# Supply_0.net
KiCad netlist of a schematic drawn in Altium Designer
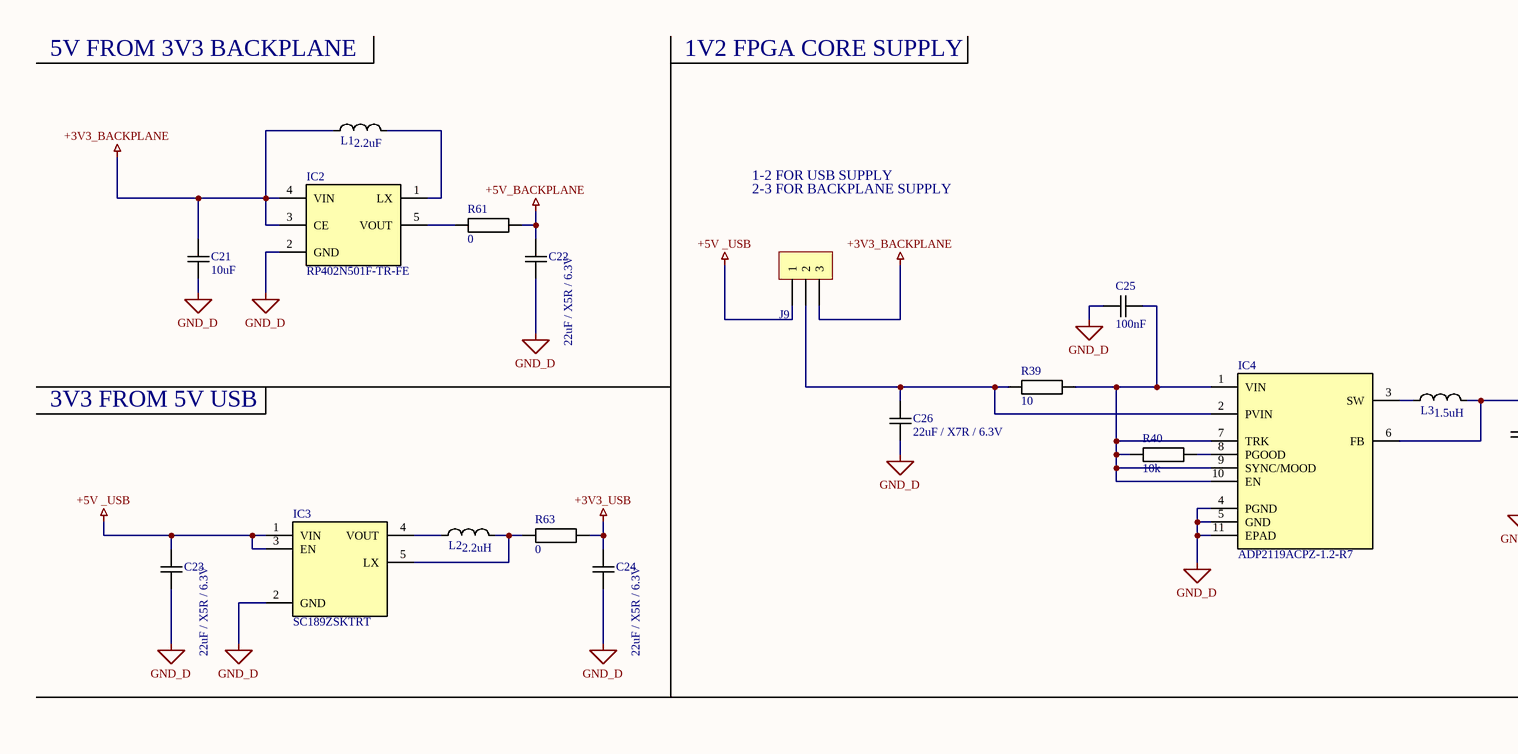
[diagram p0: Supply_0.SchDoc, left]
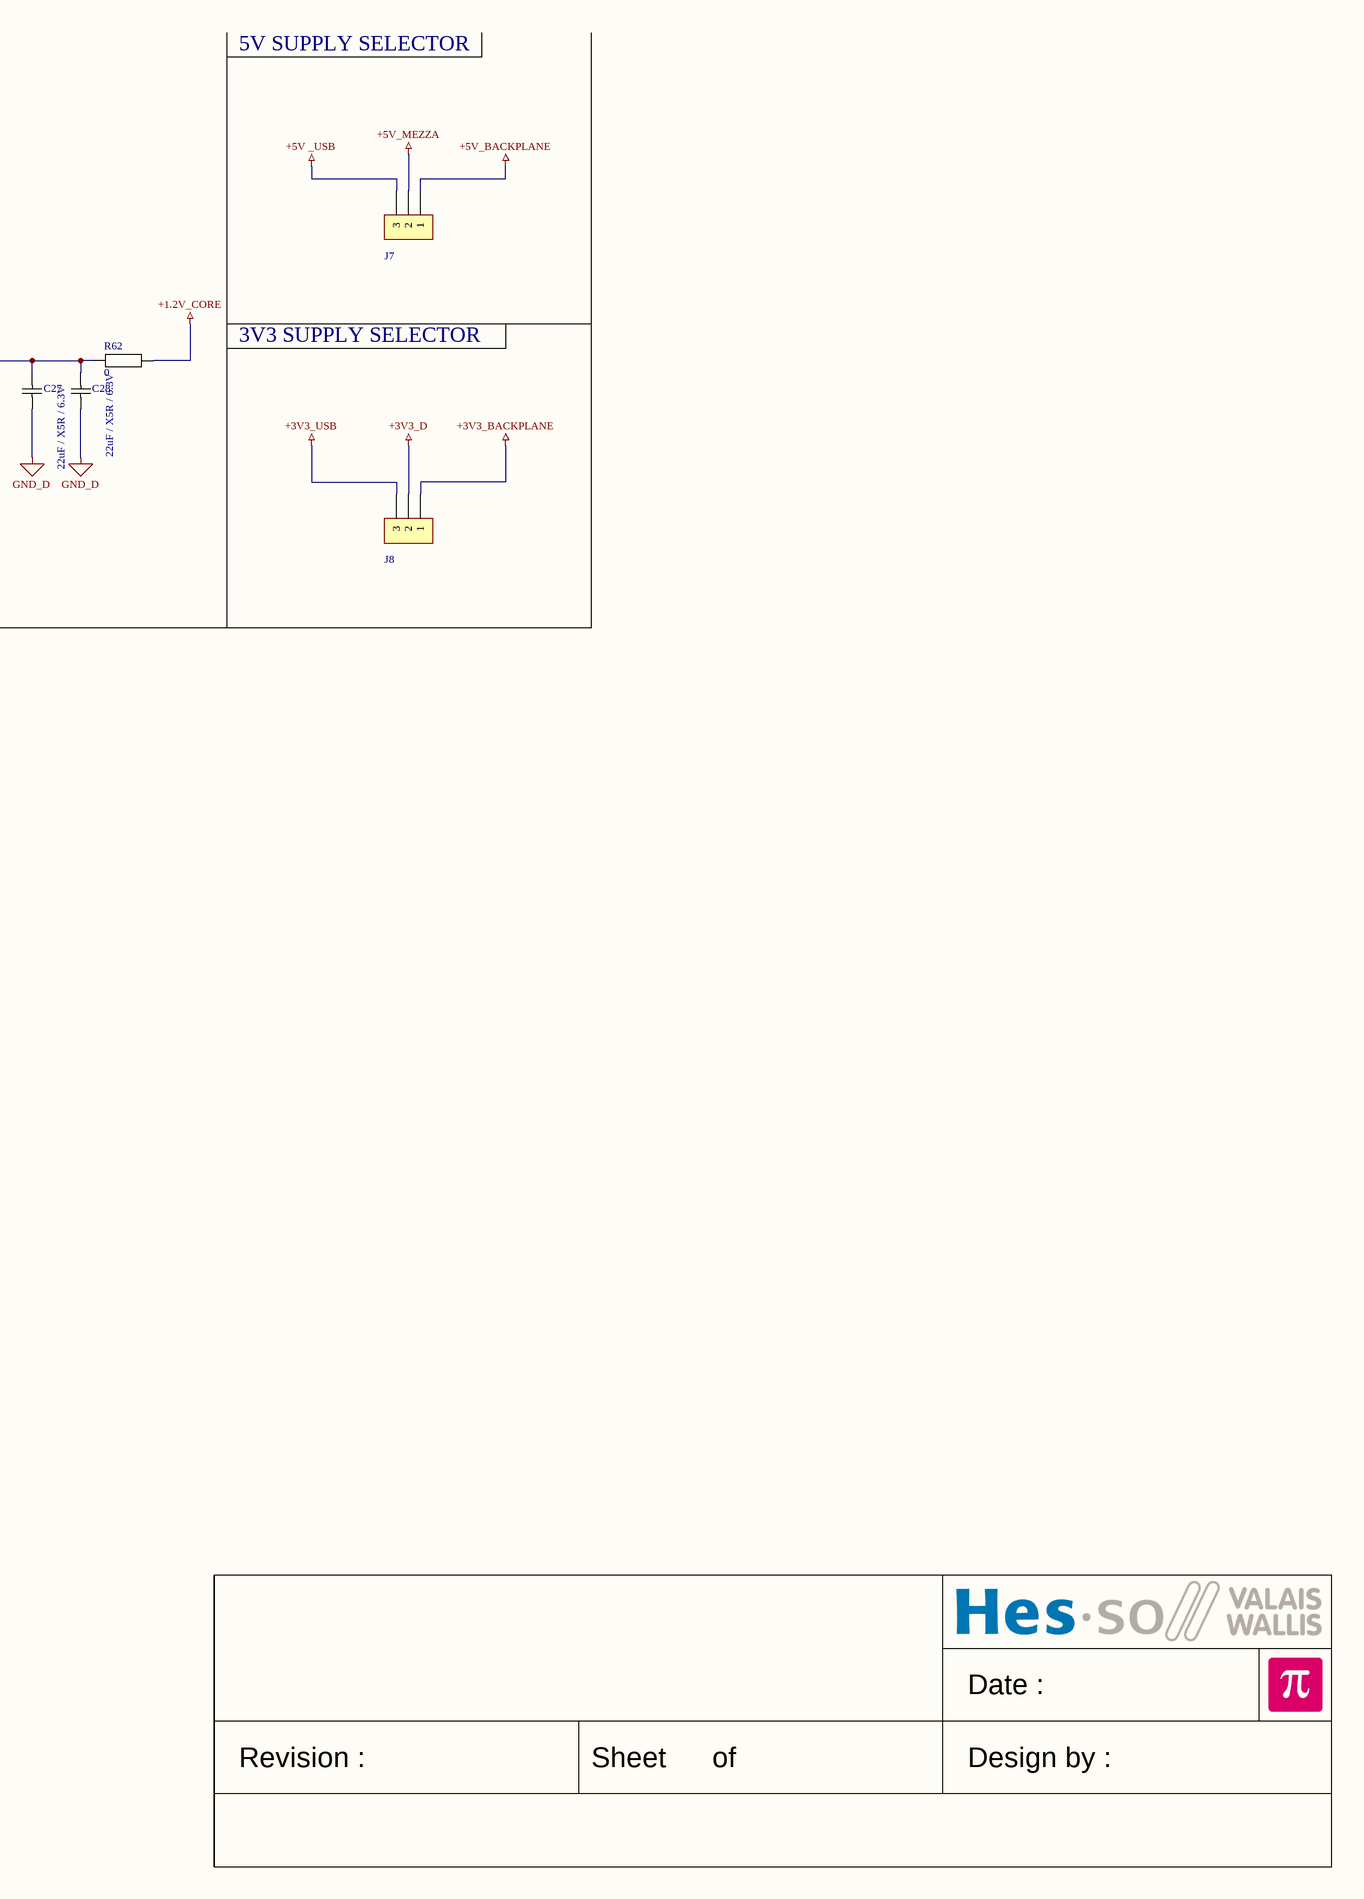
[diagram p1: Supply_0.SchDoc, right]

(export (version "E")
  (design (tool "Eeschema 10.0.6"))
  (components
    (comp (ref "C21")
      (value "10uF")
      (footprint "CAPACITOR 2012 REFLOW")
      (description "Capacitor")
      (libsource (lib "Capacitor") (part "Capacitor"))
    )
    (comp (ref "C22")
      (value "22uF / X5R / 6.3V")
      (footprint "CAPACITOR 2012 REFLOW")
      (description "Capacitor")
      (libsource (lib "Capacitor") (part "Capacitor"))
    )
    (comp (ref "C23")
      (value "22uF / X5R / 6.3V")
      (footprint "CAPACITOR 2012 REFLOW")
      (description "Capacitor")
      (libsource (lib "Capacitor") (part "Capacitor"))
    )
    (comp (ref "C24")
      (value "22uF / X5R / 6.3V")
      (footprint "CAPACITOR 2012 REFLOW")
      (description "Capacitor")
      (libsource (lib "Capacitor") (part "Capacitor"))
    )
    (comp (ref "C25")
      (value "100nF")
      (footprint "CAPACITOR 1608 REFLOW")
      (description "Capacitor")
      (libsource (lib "Capacitor") (part "Capacitor"))
    )
    (comp (ref "C26")
      (value "22uF / X7R / 6.3V")
      (footprint "CAPACITOR 2012 REFLOW")
      (description "Capacitor")
      (libsource (lib "Capacitor") (part "Capacitor"))
    )
    (comp (ref "C27")
      (value "22uF / X5R / 6.3V")
      (footprint "CAPACITOR 2012 REFLOW")
      (description "Capacitor")
      (libsource (lib "Capacitor") (part "Capacitor"))
    )
    (comp (ref "C28")
      (value "22uF / X5R / 6.3V")
      (footprint "CAPACITOR 2012 REFLOW")
      (description "Capacitor")
      (libsource (lib "Capacitor") (part "Capacitor"))
    )
    (comp (ref "IC2")
      (value "RP402N501F-TR-FE")
      (footprint "SamacSys:SOT95P280X130-5N")
      (description "Integrated Circuit")
      (fields (field (name "MOUSER PART NUMBER") "848-RP402N501F-TR-FE"))
      (libsource (lib "SamacSys") (part "RP402N501F-TR-FE"))
    )
    (comp (ref "IC3")
      (value "SC189ZSKTRT")
      (footprint "SamacSys:SOT95P280X145-5N")
      (description "Integrated Circuit")
      (fields (field (name "MOUSER PART NUMBER") "947-SC189ZSKTRT"))
      (libsource (lib "SamacSys") (part "SC189ZSKTRT"))
    )
    (comp (ref "IC4")
      (value "ADP2119ACPZ-1.2-R7")
      (footprint "SamacSys:SON50P300X300X85-11N")
      (description "Integrated Circuit")
      (fields (field (name "MOUSER PART NUMBER") "584-ADP2119ACPZ1.2R7"))
      (libsource (lib "SamacSys") (part "ADP2119ACPZ-1.2-R7"))
    )
    (comp (ref "J7")
      (value "*")
      (footprint "PinHeader1x3 P2.54")
      (description "Plug connector")
      (libsource (lib "PinHeader") (part "PinHeader1x3"))
    )
    (comp (ref "J8")
      (value "*")
      (footprint "PinHeader1x3 P2.54")
      (description "Plug connector")
      (libsource (lib "PinHeader") (part "PinHeader1x3"))
    )
    (comp (ref "J9")
      (value "*")
      (footprint "PinHeader1x3 P2.54")
      (description "Plug connector")
      (libsource (lib "") (part "PinHeader1x3_1"))
    )
    (comp (ref "L1")
      (value "2.2uF")
      (footprint "TDK VLCF5020-1")
      (description "Inductor")
      (libsource (lib "Inductor") (part "Inductor"))
    )
    (comp (ref "L2")
      (value "2.2uH")
      (footprint "TDK VLCF5020-1")
      (description "Inductor")
      (libsource (lib "Inductor") (part "Inductor"))
    )
    (comp (ref "L3")
      (value "1.5uH")
      (footprint "TDK VLCF5020-1")
      (description "Inductor")
      (libsource (lib "Inductor") (part "Inductor"))
    )
    (comp (ref "R39")
      (value "10")
      (footprint "RESISTOR 2012 REFLOW")
      (description "Resistor 1% 50V 125mW 2012(0805)")
      (libsource (lib "Resistor") (part "Resistor"))
    )
    (comp (ref "R40")
      (value "10k")
      (footprint "RESISTOR 2012 REFLOW")
      (description "Resistor 1% 50V 125mW 2012(0805)")
      (libsource (lib "Resistor") (part "Resistor"))
    )
    (comp (ref "R61")
      (value "0")
      (footprint "RESISTOR 1608 REFLOW")
      (description "Resistor 1% 50V 100mW 1608(0603)")
      (libsource (lib "Resistor") (part "Resistor"))
    )
    (comp (ref "R62")
      (value "0")
      (footprint "RESISTOR 1608 REFLOW")
      (description "Resistor 1% 50V 100mW 1608(0603)")
      (libsource (lib "Resistor") (part "Resistor"))
    )
    (comp (ref "R63")
      (value "0")
      (footprint "RESISTOR 1608 REFLOW")
      (description "Resistor 1% 50V 100mW 1608(0603)")
      (libsource (lib "Resistor") (part "Resistor"))
    )
  )
  (nets
    (net (code "1") (name "+1.2V_CORE") (class "Default")
      (node (ref "R62") (pin "2") (pinfunction "2_2") (pintype "passive"))
    )
    (net (code "2") (name "+3V3_BACKPLANE") (class "Default")
      (node (ref "C21") (pin "2") (pinfunction "2_2") (pintype "passive"))
      (node (ref "IC2") (pin "3") (pinfunction "CE_3") (pintype "passive"))
      (node (ref "IC2") (pin "4") (pinfunction "VIN_4") (pintype "passive"))
      (node (ref "J8") (pin "1") (pinfunction "1_1") (pintype "passive"))
      (node (ref "J9") (pin "3") (pinfunction "3_3") (pintype "passive"))
      (node (ref "L1") (pin "1") (pinfunction "1_1") (pintype "passive"))
    )
    (net (code "3") (name "+3V3_D") (class "Default")
      (node (ref "J8") (pin "2") (pinfunction "2_2") (pintype "passive"))
    )
    (net (code "4") (name "+3V3_USB") (class "Default")
      (node (ref "C24") (pin "2") (pinfunction "2_2") (pintype "passive"))
      (node (ref "J8") (pin "3") (pinfunction "3_3") (pintype "passive"))
      (node (ref "R63") (pin "2") (pinfunction "2_2") (pintype "passive"))
    )
    (net (code "5") (name "+5V _USB") (class "Default")
      (node (ref "C23") (pin "2") (pinfunction "2_2") (pintype "passive"))
      (node (ref "IC3") (pin "1") (pinfunction "VIN_1") (pintype "passive"))
      (node (ref "IC3") (pin "3") (pinfunction "EN_3") (pintype "passive"))
      (node (ref "J7") (pin "3") (pinfunction "3_3") (pintype "passive"))
      (node (ref "J9") (pin "1") (pinfunction "1_1") (pintype "passive"))
    )
    (net (code "6") (name "+5V_BACKPLANE") (class "Default")
      (node (ref "C22") (pin "2") (pinfunction "2_2") (pintype "passive"))
      (node (ref "J7") (pin "1") (pinfunction "1_1") (pintype "passive"))
      (node (ref "R61") (pin "2") (pinfunction "2_2") (pintype "passive"))
    )
    (net (code "7") (name "+5V_MEZZA") (class "Default")
      (node (ref "J7") (pin "2") (pinfunction "2_2") (pintype "passive"))
    )
    (net (code "8") (name "GND_D") (class "Default")
      (node (ref "C21") (pin "1") (pinfunction "1_1") (pintype "passive"))
      (node (ref "C22") (pin "1") (pinfunction "1_1") (pintype "passive"))
      (node (ref "C23") (pin "1") (pinfunction "1_1") (pintype "passive"))
      (node (ref "C24") (pin "1") (pinfunction "1_1") (pintype "passive"))
      (node (ref "C25") (pin "2") (pinfunction "2_2") (pintype "passive"))
      (node (ref "C26") (pin "1") (pinfunction "1_1") (pintype "passive"))
      (node (ref "C27") (pin "1") (pinfunction "1_1") (pintype "passive"))
      (node (ref "C28") (pin "1") (pinfunction "1_1") (pintype "passive"))
      (node (ref "IC2") (pin "2") (pinfunction "GND_2") (pintype "passive"))
      (node (ref "IC3") (pin "2") (pinfunction "GND_2") (pintype "passive"))
      (node (ref "IC4") (pin "11") (pinfunction "EPAD_11") (pintype "passive"))
      (node (ref "IC4") (pin "4") (pinfunction "PGND_4") (pintype "passive"))
      (node (ref "IC4") (pin "5") (pinfunction "GND_5") (pintype "passive"))
    )
    (net (code "9") (name "Net-(IC2-LX)") (class "Default")
      (node (ref "IC2") (pin "1") (pinfunction "LX_1") (pintype "passive"))
      (node (ref "L1") (pin "2") (pinfunction "2_2") (pintype "passive"))
    )
    (net (code "10") (name "Net-(IC2-VOUT)") (class "Default")
      (node (ref "IC2") (pin "5") (pinfunction "VOUT_5") (pintype "passive"))
      (node (ref "R61") (pin "1") (pinfunction "1_1") (pintype "passive"))
    )
    (net (code "11") (name "Net-(IC3-LX)") (class "Default")
      (node (ref "IC3") (pin "5") (pinfunction "LX_5") (pintype "passive"))
      (node (ref "L2") (pin "2") (pinfunction "2_2") (pintype "passive"))
      (node (ref "R63") (pin "1") (pinfunction "1_1") (pintype "passive"))
    )
    (net (code "12") (name "Net-(IC3-VOUT)") (class "Default")
      (node (ref "IC3") (pin "4") (pinfunction "VOUT_4") (pintype "passive"))
      (node (ref "L2") (pin "1") (pinfunction "1_1") (pintype "passive"))
    )
    (net (code "13") (name "Net-(IC4-EN)") (class "Default")
      (node (ref "C25") (pin "1") (pinfunction "1_1") (pintype "passive"))
      (node (ref "IC4") (pin "1") (pinfunction "VIN_1") (pintype "passive"))
      (node (ref "IC4") (pin "10") (pinfunction "EN_10") (pintype "passive"))
      (node (ref "IC4") (pin "7") (pinfunction "TRK_7") (pintype "passive"))
      (node (ref "IC4") (pin "9") (pinfunction "SYNC/MOOD_9") (pintype "passive"))
      (node (ref "R39") (pin "1") (pinfunction "1_1") (pintype "passive"))
      (node (ref "R40") (pin "2") (pinfunction "2_2") (pintype "passive"))
    )
    (net (code "14") (name "Net-(IC4-FB)") (class "Default")
      (node (ref "C27") (pin "2") (pinfunction "2_2") (pintype "passive"))
      (node (ref "C28") (pin "2") (pinfunction "2_2") (pintype "passive"))
      (node (ref "IC4") (pin "6") (pinfunction "FB_6") (pintype "passive"))
      (node (ref "L3") (pin "2") (pinfunction "2_2") (pintype "passive"))
      (node (ref "R62") (pin "1") (pinfunction "1_1") (pintype "passive"))
    )
    (net (code "15") (name "Net-(IC4-PGOOD)") (class "Default")
      (node (ref "IC4") (pin "8") (pinfunction "PGOOD_8") (pintype "passive"))
      (node (ref "R40") (pin "1") (pinfunction "1_1") (pintype "passive"))
    )
    (net (code "16") (name "Net-(IC4-PVIN)") (class "Default")
      (node (ref "C26") (pin "2") (pinfunction "2_2") (pintype "passive"))
      (node (ref "IC4") (pin "2") (pinfunction "PVIN_2") (pintype "passive"))
      (node (ref "J9") (pin "2") (pinfunction "2_2") (pintype "passive"))
      (node (ref "R39") (pin "2") (pinfunction "2_2") (pintype "passive"))
    )
    (net (code "17") (name "Net-(IC4-SW)") (class "Default")
      (node (ref "IC4") (pin "3") (pinfunction "SW_3") (pintype "passive"))
      (node (ref "L3") (pin "1") (pinfunction "1_1") (pintype "passive"))
    )
  )
)
